# DualBalancedInput.net
KiCad netlist of a schematic drawn in EAGLE
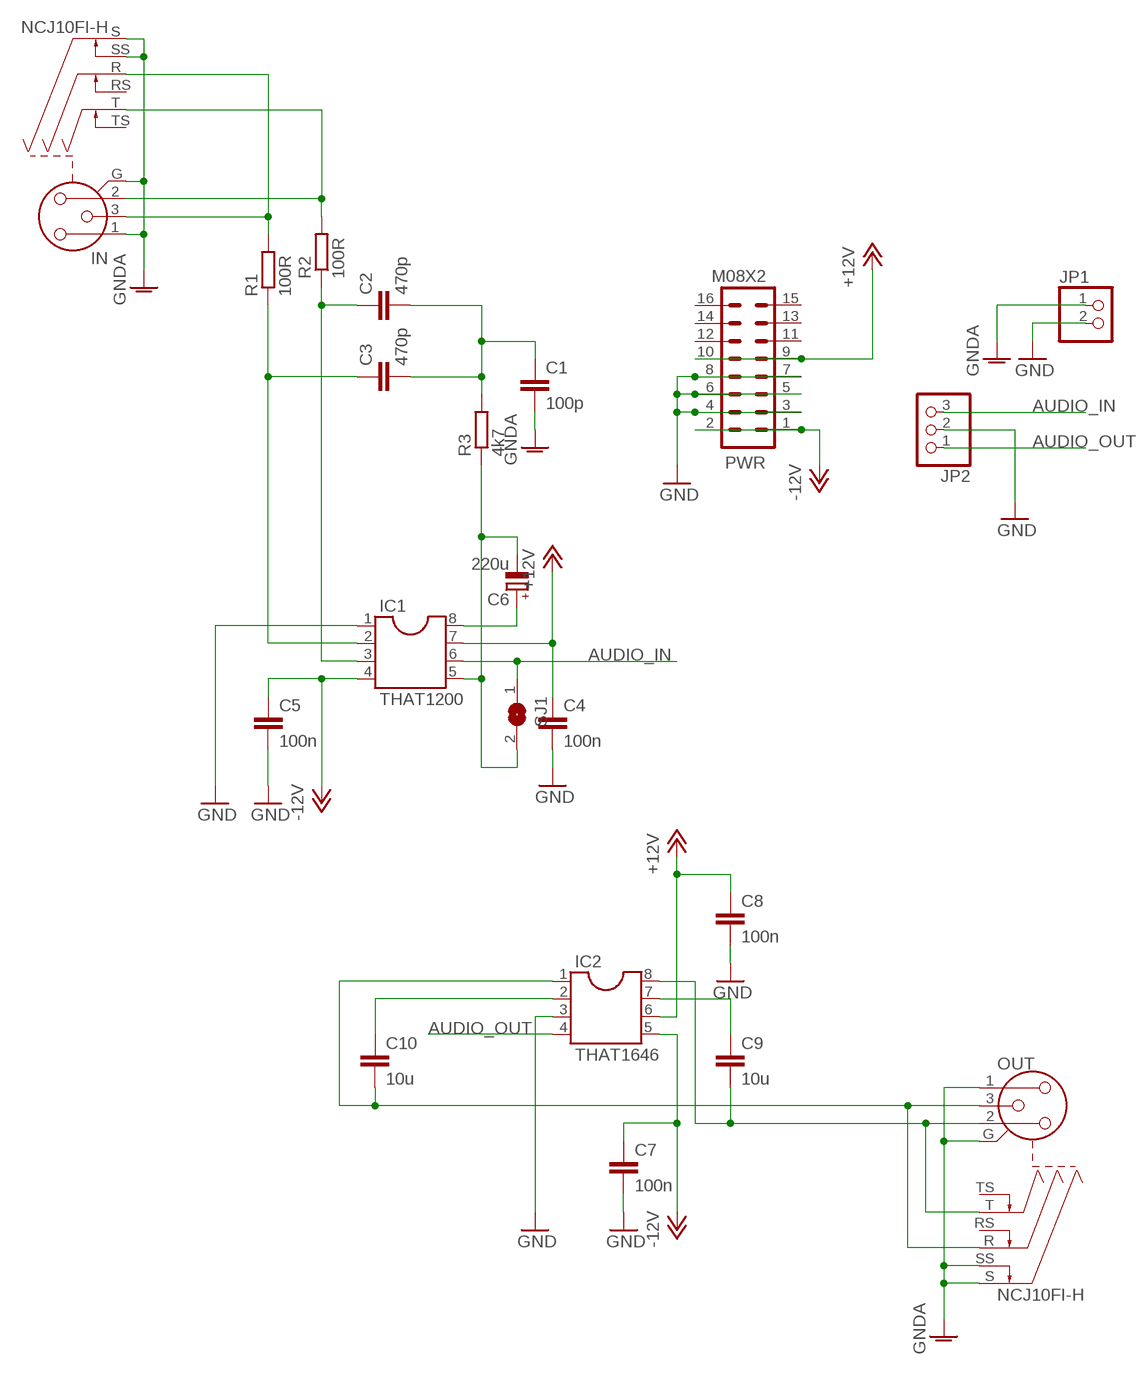
[diagram p0: schematic, sheet 1]

(export (version "E")
  (design (tool "Eeschema 10.0.6"))
  (components
    (comp (ref "C1")
      (value "100p")
      (footprint "eagle-import:C050-025X075")
      (libsource (lib "eagle-import") (part "C-EU050-025X075"))
    )
    (comp (ref "C2")
      (value "470p")
      (footprint "eagle-import:C050-025X075")
      (libsource (lib "eagle-import") (part "C-EU050-025X075"))
    )
    (comp (ref "C3")
      (value "470p")
      (footprint "eagle-import:C050-025X075")
      (libsource (lib "eagle-import") (part "C-EU050-025X075"))
    )
    (comp (ref "C4")
      (value "100n")
      (footprint "eagle-import:C050-025X075")
      (libsource (lib "eagle-import") (part "C-EU050-025X075"))
    )
    (comp (ref "C5")
      (value "100n")
      (footprint "eagle-import:C050-025X075")
      (libsource (lib "eagle-import") (part "C-EU050-025X075"))
    )
    (comp (ref "C6")
      (value "220u")
      (footprint "eagle-import:E5-8,5")
      (libsource (lib "eagle-import") (part "CPOL-EUE5-8.5"))
    )
    (comp (ref "C7")
      (value "100n")
      (footprint "eagle-import:C050-025X075")
      (libsource (lib "eagle-import") (part "C-EU050-025X075"))
    )
    (comp (ref "C8")
      (value "100n")
      (footprint "eagle-import:C050-025X075")
      (libsource (lib "eagle-import") (part "C-EU050-025X075"))
    )
    (comp (ref "C9")
      (value "10u")
      (footprint "eagle-import:C050-025X075")
      (libsource (lib "eagle-import") (part "C-EU050-025X075"))
    )
    (comp (ref "C10")
      (value "10u")
      (footprint "eagle-import:C050-025X075")
      (libsource (lib "eagle-import") (part "C-EU050-025X075"))
    )
    (comp (ref "IC1")
      (value "THAT1200")
      (footprint "eagle-import:DIL08")
      (libsource (lib "eagle-import") (part "DIL8"))
    )
    (comp (ref "IC2")
      (value "THAT1646")
      (footprint "eagle-import:DIL08")
      (libsource (lib "eagle-import") (part "DIL8"))
    )
    (comp (ref "IN")
      (value "NCJ10FI-H")
      (footprint "eagle-import:NCJ10FI-H")
      (libsource (lib "eagle-import") (part "NCJ10FI-H"))
    )
    (comp (ref "JP1")
      (value "PINHD-1X2")
      (footprint "eagle-import:1X02")
      (libsource (lib "eagle-import") (part "PINHD-1X2"))
    )
    (comp (ref "JP2")
      (value "PINHD-1X3")
      (footprint "eagle-import:1X03")
      (libsource (lib "eagle-import") (part "PINHD-1X3"))
    )
    (comp (ref "OUT")
      (value "NCJ10FI-H")
      (footprint "eagle-import:NCJ10FI-H")
      (libsource (lib "eagle-import") (part "NCJ10FI-H"))
    )
    (comp (ref "PWR")
      (value "M08X2")
      (footprint "eagle-import:2X8")
      (libsource (lib "eagle-import") (part "M08X2"))
    )
    (comp (ref "R1")
      (value "100R")
      (footprint "eagle-import:0207_7")
      (libsource (lib "eagle-import") (part "R-EU_0207/7"))
    )
    (comp (ref "R2")
      (value "100R")
      (footprint "eagle-import:0207_7")
      (libsource (lib "eagle-import") (part "R-EU_0207/7"))
    )
    (comp (ref "R3")
      (value "4k7")
      (footprint "eagle-import:0207_7")
      (libsource (lib "eagle-import") (part "R-EU_0207/7"))
    )
    (comp (ref "SJ1")
      (value "SJW")
      (footprint "eagle-import:SJW")
      (libsource (lib "eagle-import") (part "SJW"))
    )
  )
  (nets
    (net (code "1") (name "+12V") (class "Default")
      (node (ref "C4") (pin "1") (pinfunction "1_1") (pintype "passive"))
      (node (ref "C8") (pin "1") (pinfunction "1_1") (pintype "passive"))
      (node (ref "IC1") (pin "7") (pinfunction "7_7") (pintype "passive"))
      (node (ref "IC2") (pin "6") (pinfunction "6_6") (pintype "passive"))
      (node (ref "PWR") (pin "10") (pinfunction "10_10") (pintype "passive"))
      (node (ref "PWR") (pin "9") (pinfunction "9_9") (pintype "passive"))
    )
    (net (code "2") (name "-12V") (class "Default")
      (node (ref "C5") (pin "1") (pinfunction "1_1") (pintype "passive"))
      (node (ref "C7") (pin "1") (pinfunction "1_1") (pintype "passive"))
      (node (ref "IC1") (pin "4") (pinfunction "4_4") (pintype "passive"))
      (node (ref "IC2") (pin "5") (pinfunction "5_5") (pintype "passive"))
      (node (ref "PWR") (pin "1") (pinfunction "1_1") (pintype "passive"))
      (node (ref "PWR") (pin "2") (pinfunction "2_2") (pintype "passive"))
    )
    (net (code "3") (name "/AUDIO_IN") (class "Default")
      (node (ref "IC1") (pin "6") (pinfunction "6_6") (pintype "passive"))
      (node (ref "JP2") (pin "3") (pinfunction "3_3") (pintype "passive"))
      (node (ref "SJ1") (pin "1") (pinfunction "1_1") (pintype "passive"))
    )
    (net (code "4") (name "/AUDIO_OUT") (class "Default")
      (node (ref "IC2") (pin "4") (pinfunction "4_4") (pintype "passive"))
      (node (ref "JP2") (pin "1") (pinfunction "1_1") (pintype "passive"))
    )
    (net (code "5") (name "GND") (class "Default")
      (node (ref "C4") (pin "2") (pinfunction "2_2") (pintype "passive"))
      (node (ref "C5") (pin "2") (pinfunction "2_2") (pintype "passive"))
      (node (ref "C7") (pin "2") (pinfunction "2_2") (pintype "passive"))
      (node (ref "C8") (pin "2") (pinfunction "2_2") (pintype "passive"))
      (node (ref "IC1") (pin "1") (pinfunction "1_1") (pintype "passive"))
      (node (ref "IC2") (pin "3") (pinfunction "3_3") (pintype "passive"))
      (node (ref "JP1") (pin "2") (pinfunction "2_2") (pintype "passive"))
      (node (ref "JP2") (pin "2") (pinfunction "2_2") (pintype "passive"))
      (node (ref "PWR") (pin "3") (pinfunction "3_3") (pintype "passive"))
      (node (ref "PWR") (pin "4") (pinfunction "4_4") (pintype "passive"))
      (node (ref "PWR") (pin "5") (pinfunction "5_5") (pintype "passive"))
      (node (ref "PWR") (pin "6") (pinfunction "6_6") (pintype "passive"))
      (node (ref "PWR") (pin "7") (pinfunction "7_7") (pintype "passive"))
      (node (ref "PWR") (pin "8") (pinfunction "8_8") (pintype "passive"))
    )
    (net (code "6") (name "GNDA") (class "Default")
      (node (ref "C1") (pin "2") (pinfunction "2_2") (pintype "passive"))
      (node (ref "IN") (pin "1") (pinfunction "1_1") (pintype "passive"))
      (node (ref "IN") (pin "G") (pinfunction "G_G") (pintype "passive"))
      (node (ref "IN") (pin "S") (pinfunction "S_S") (pintype "passive"))
      (node (ref "IN") (pin "SS") (pinfunction "SS_SS") (pintype "passive"))
      (node (ref "JP1") (pin "1") (pinfunction "1_1") (pintype "passive"))
      (node (ref "OUT") (pin "1") (pinfunction "1_1") (pintype "passive"))
      (node (ref "OUT") (pin "G") (pinfunction "G_G") (pintype "passive"))
      (node (ref "OUT") (pin "S") (pinfunction "S_S") (pintype "passive"))
      (node (ref "OUT") (pin "SS") (pinfunction "SS_SS") (pintype "passive"))
    )
    (net (code "7") (name "Net-(C1-Pad1)") (class "Default")
      (node (ref "C1") (pin "1") (pinfunction "1_1") (pintype "passive"))
      (node (ref "C2") (pin "2") (pinfunction "2_2") (pintype "passive"))
      (node (ref "C3") (pin "2") (pinfunction "2_2") (pintype "passive"))
      (node (ref "R3") (pin "2") (pinfunction "2_2") (pintype "passive"))
    )
    (net (code "8") (name "Net-(C2-Pad1)") (class "Default")
      (node (ref "C2") (pin "1") (pinfunction "1_1") (pintype "passive"))
      (node (ref "IC1") (pin "3") (pinfunction "3_3") (pintype "passive"))
      (node (ref "R2") (pin "1") (pinfunction "1_1") (pintype "passive"))
    )
    (net (code "9") (name "Net-(C3-Pad1)") (class "Default")
      (node (ref "C3") (pin "1") (pinfunction "1_1") (pintype "passive"))
      (node (ref "IC1") (pin "2") (pinfunction "2_2") (pintype "passive"))
      (node (ref "R1") (pin "1") (pinfunction "1_1") (pintype "passive"))
    )
    (net (code "10") (name "Net-(C6-Pad+)") (class "Default")
      (node (ref "C6") (pin "+") (pinfunction "+_+") (pintype "passive"))
      (node (ref "IC1") (pin "8") (pinfunction "8_8") (pintype "passive"))
    )
    (net (code "11") (name "Net-(C6-Pad-)") (class "Default")
      (node (ref "C6") (pin "-") (pinfunction "-_-") (pintype "passive"))
      (node (ref "IC1") (pin "5") (pinfunction "5_5") (pintype "passive"))
      (node (ref "R3") (pin "1") (pinfunction "1_1") (pintype "passive"))
      (node (ref "SJ1") (pin "2") (pinfunction "2_2") (pintype "passive"))
    )
    (net (code "12") (name "Net-(C9-Pad1)") (class "Default")
      (node (ref "C9") (pin "1") (pinfunction "1_1") (pintype "passive"))
      (node (ref "IC2") (pin "7") (pinfunction "7_7") (pintype "passive"))
    )
    (net (code "13") (name "Net-(C9-Pad2)") (class "Default")
      (node (ref "C9") (pin "2") (pinfunction "2_2") (pintype "passive"))
      (node (ref "IC2") (pin "8") (pinfunction "8_8") (pintype "passive"))
      (node (ref "OUT") (pin "2") (pinfunction "2_2") (pintype "passive"))
      (node (ref "OUT") (pin "T") (pinfunction "T_T") (pintype "passive"))
    )
    (net (code "14") (name "Net-(C10-Pad1)") (class "Default")
      (node (ref "C10") (pin "1") (pinfunction "1_1") (pintype "passive"))
      (node (ref "IC2") (pin "2") (pinfunction "2_2") (pintype "passive"))
    )
    (net (code "15") (name "Net-(C10-Pad2)") (class "Default")
      (node (ref "C10") (pin "2") (pinfunction "2_2") (pintype "passive"))
      (node (ref "IC2") (pin "1") (pinfunction "1_1") (pintype "passive"))
      (node (ref "OUT") (pin "3") (pinfunction "3_3") (pintype "passive"))
      (node (ref "OUT") (pin "R") (pinfunction "R_R") (pintype "passive"))
    )
    (net (code "16") (name "Net-(IN-Pad2)") (class "Default")
      (node (ref "IN") (pin "2") (pinfunction "2_2") (pintype "passive"))
      (node (ref "IN") (pin "T") (pinfunction "T_T") (pintype "passive"))
      (node (ref "R2") (pin "2") (pinfunction "2_2") (pintype "passive"))
    )
    (net (code "17") (name "Net-(IN-Pad3)") (class "Default")
      (node (ref "IN") (pin "3") (pinfunction "3_3") (pintype "passive"))
      (node (ref "IN") (pin "R") (pinfunction "R_R") (pintype "passive"))
      (node (ref "R1") (pin "2") (pinfunction "2_2") (pintype "passive"))
    )
    (net (code "18") (name "unconnected-(IN-PadRS)") (class "Default")
      (node (ref "IN") (pin "RS") (pinfunction "RS_RS") (pintype "passive"))
    )
    (net (code "19") (name "unconnected-(IN-PadTS)") (class "Default")
      (node (ref "IN") (pin "TS") (pinfunction "TS_TS") (pintype "passive"))
    )
    (net (code "20") (name "unconnected-(OUT-PadRS)") (class "Default")
      (node (ref "OUT") (pin "RS") (pinfunction "RS_RS") (pintype "passive"))
    )
    (net (code "21") (name "unconnected-(OUT-PadTS)") (class "Default")
      (node (ref "OUT") (pin "TS") (pinfunction "TS_TS") (pintype "passive"))
    )
    (net (code "22") (name "unconnected-(PWR-Pad11)") (class "Default")
      (node (ref "PWR") (pin "11") (pinfunction "11_11") (pintype "passive"))
    )
    (net (code "23") (name "unconnected-(PWR-Pad12)") (class "Default")
      (node (ref "PWR") (pin "12") (pinfunction "12_12") (pintype "passive"))
    )
    (net (code "24") (name "unconnected-(PWR-Pad13)") (class "Default")
      (node (ref "PWR") (pin "13") (pinfunction "13_13") (pintype "passive"))
    )
    (net (code "25") (name "unconnected-(PWR-Pad14)") (class "Default")
      (node (ref "PWR") (pin "14") (pinfunction "14_14") (pintype "passive"))
    )
    (net (code "26") (name "unconnected-(PWR-Pad15)") (class "Default")
      (node (ref "PWR") (pin "15") (pinfunction "15_15") (pintype "passive"))
    )
    (net (code "27") (name "unconnected-(PWR-Pad16)") (class "Default")
      (node (ref "PWR") (pin "16") (pinfunction "16_16") (pintype "passive"))
    )
  )
)
